# 51.net
KiCad netlist of a schematic drawn in Altium Designer
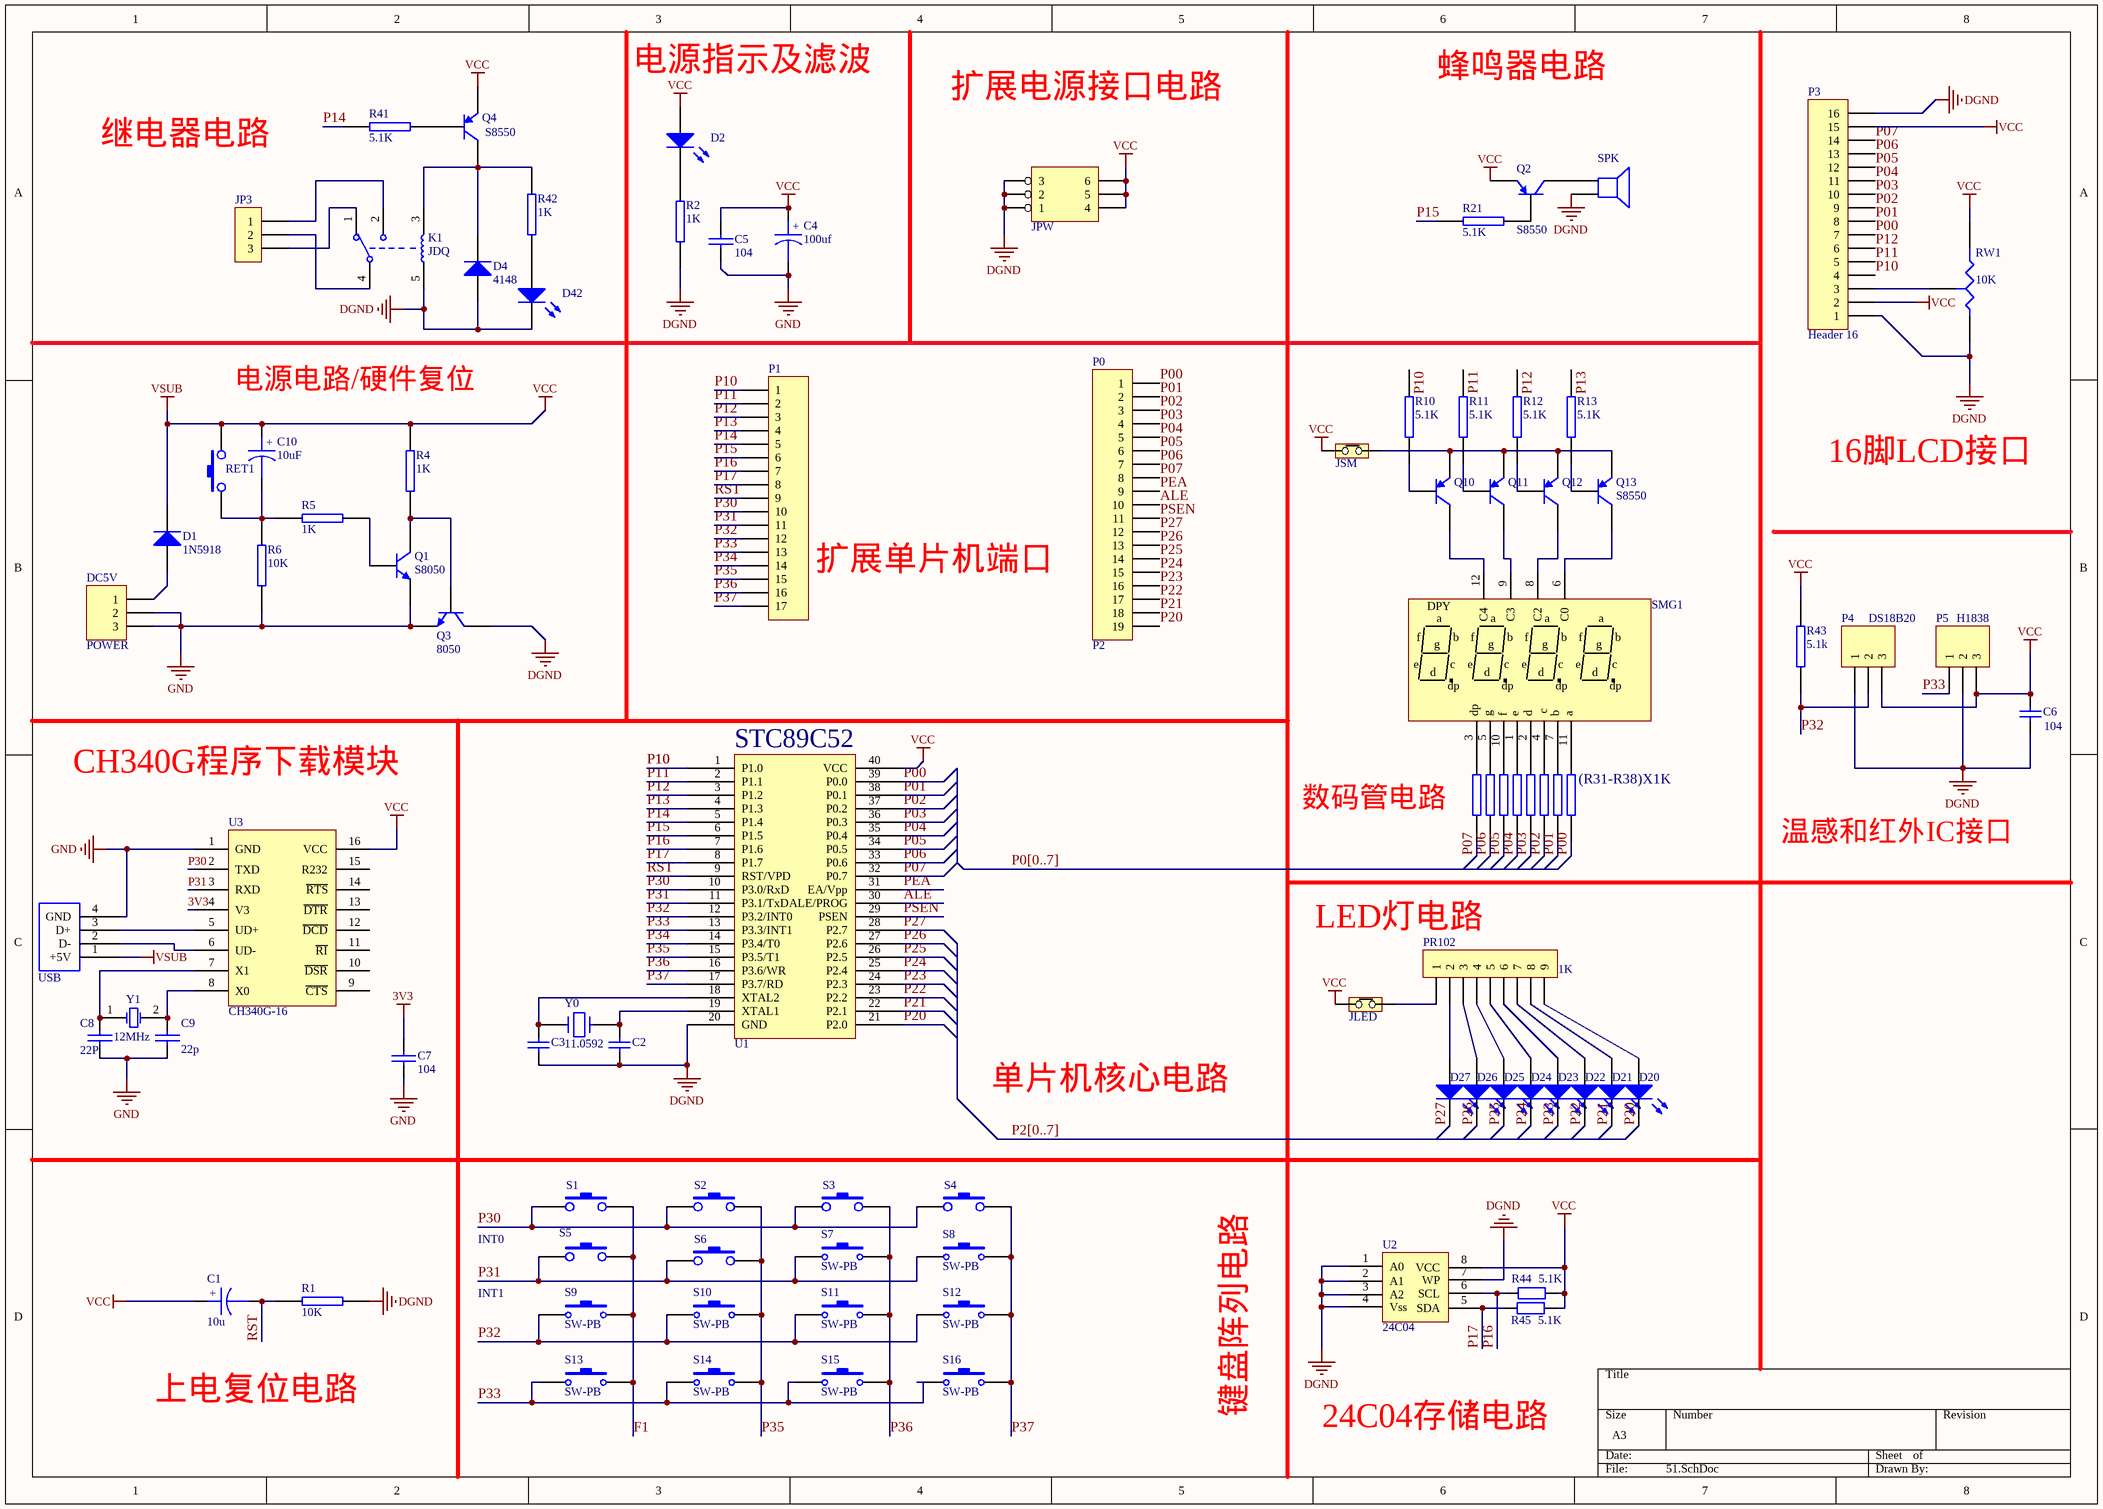
[diagram p0: 51.SchDoc]

(export (version "E")
  (design (tool "Eeschema 10.0.6"))
  (components
    (comp (ref "C1")
      (value "10u")
      (footprint "C2")
      (description "Capacitor")
      (libsource (lib "1") (part "CAPACITOR POL"))
    )
    (comp (ref "C2")
      (value "Cap")
      (footprint "RAD-0.1")
      (description "Capacitor")
      (fields
        (field (name "MANUFACTURER") "Generic Components")
        (field (name "PUBLISHER") "Altium Hobart Technology Centre")
      )
      (libsource (lib "Miscellaneous Devices") (part "Cap"))
    )
    (comp (ref "C3")
      (value "Cap")
      (footprint "RAD-0.1")
      (description "Capacitor")
      (fields
        (field (name "MANUFACTURER") "Generic Components")
        (field (name "PUBLISHER") "Altium Hobart Technology Centre")
      )
      (libsource (lib "Miscellaneous Devices") (part "Cap"))
    )
    (comp (ref "C4")
      (value "100uf")
      (footprint "c4")
      (description "Capacitor")
      (libsource (lib "1") (part "CAPACITOR POL"))
    )
    (comp (ref "C5")
      (value "104")
      (footprint "RAD-0.1")
      (description "Capacitor")
      (libsource (lib "1") (part "CAP"))
    )
    (comp (ref "C6")
      (value "104")
      (footprint "RAD-0.1")
      (description "Capacitor")
      (fields (field (name "Comment") "Cap") (field (name "PUBLISHER") "Altium Limited"))
      (libsource (lib "Miscellaneous Devices") (part "Cap"))
    )
    (comp (ref "C7")
      (value "104")
      (footprint "RAD-0.1")
      (description "Capacitor")
      (libsource (lib "Miscellaneous Devices") (part "CAP"))
    )
    (comp (ref "C8")
      (value "22P")
      (footprint "RAD-0.1")
      (description "Capacitor")
      (libsource (lib "Miscellaneous Devices") (part "CAP"))
    )
    (comp (ref "C9")
      (value "22p")
      (footprint "RAD-0.1")
      (description "Capacitor")
      (libsource (lib "Miscellaneous Devices") (part "CAP"))
    )
    (comp (ref "C10")
      (value "10uF")
      (footprint "c4")
      (description "Capacitor")
      (libsource (lib "1") (part "CAPACITOR POL"))
    )
    (comp (ref "D1")
      (value "1N5918")
      (footprint "4148")
      (description "3 Amp Medium Power Silicon Rectifier Diode")
      (fields (field (name "PUBLISHER") "Altium Limited"))
      (libsource (lib "Miscellaneous Devices") (part "Diode 1N5408"))
    )
    (comp (ref "D2")
      (value "LED0")
      (footprint "LED2")
      (description "Typical INFRARED GaAs LED")
      (fields (field (name "PUBLISHER") "Altium Limited"))
      (libsource (lib "Miscellaneous Devices") (part "LED0"))
    )
    (comp (ref "D4")
      (value "4148")
      (footprint "DO-41")
      (description "1 Amp General Purpose Rectifier")
      (fields (field (name "PUBLISHER") "Altium Limited"))
      (libsource (lib "Miscellaneous Devices") (part "Diode 1N4001"))
    )
    (comp (ref "D20")
      (value "LED0")
      (footprint "LED8")
      (description "Typical INFRARED GaAs LED")
      (fields (field (name "PUBLISHER") "Altium Limited"))
      (libsource (lib "Miscellaneous Devices") (part "LED0"))
    )
    (comp (ref "D21")
      (value "LED0")
      (footprint "LED8")
      (description "Typical INFRARED GaAs LED")
      (fields (field (name "PUBLISHER") "Altium Limited"))
      (libsource (lib "Miscellaneous Devices") (part "LED0"))
    )
    (comp (ref "D22")
      (value "LED0")
      (footprint "LED8")
      (description "Typical INFRARED GaAs LED")
      (fields (field (name "PUBLISHER") "Altium Limited"))
      (libsource (lib "Miscellaneous Devices") (part "LED0"))
    )
    (comp (ref "D23")
      (value "LED0")
      (footprint "LED8")
      (description "Typical INFRARED GaAs LED")
      (fields (field (name "PUBLISHER") "Altium Limited"))
      (libsource (lib "Miscellaneous Devices") (part "LED0"))
    )
    (comp (ref "D24")
      (value "LED0")
      (footprint "LED8")
      (description "Typical INFRARED GaAs LED")
      (fields (field (name "PUBLISHER") "Altium Limited"))
      (libsource (lib "Miscellaneous Devices") (part "LED0"))
    )
    (comp (ref "D25")
      (value "LED0")
      (footprint "LED8")
      (description "Typical INFRARED GaAs LED")
      (fields (field (name "PUBLISHER") "Altium Limited"))
      (libsource (lib "Miscellaneous Devices") (part "LED0"))
    )
    (comp (ref "D26")
      (value "LED0")
      (footprint "LED8")
      (description "Typical INFRARED GaAs LED")
      (fields (field (name "PUBLISHER") "Altium Limited"))
      (libsource (lib "Miscellaneous Devices") (part "LED0"))
    )
    (comp (ref "D27")
      (value "LED0")
      (footprint "LED8")
      (description "Typical INFRARED GaAs LED")
      (fields (field (name "PUBLISHER") "Altium Limited"))
      (libsource (lib "Miscellaneous Devices") (part "LED0"))
    )
    (comp (ref "D42")
      (value "LED0")
      (footprint "LED2")
      (description "Typical INFRARED GaAs LED")
      (fields (field (name "PUBLISHER") "Altium Limited"))
      (libsource (lib "Miscellaneous Devices") (part "LED0"))
    )
    (comp (ref "DC5V")
      (value "POWER")
      (footprint "DC5V-3")
      (description "Header, 3-Pin")
      (fields (field (name "PUBLISHER") "Altium Limited"))
      (libsource (lib "Miscellaneous Connectors") (part "Header 3"))
    )
    (comp (ref "JLED") (value "JJ") (footprint "j2") (libsource (lib "51单片机24_1") (part "JJ")))
    (comp (ref "JP3") (value "JP3") (footprint "JP3") (libsource (lib "51单片机24") (part "JP3")))
    (comp (ref "JPW") (value "JPW") (footprint "SIP") (libsource (lib "51单片机24_1") (part "JPW")))
    (comp (ref "JSM") (value "JJ") (footprint "j2") (libsource (lib "51单片机24_1") (part "JJ")))
    (comp (ref "K1") (value "JDQ") (footprint "JDQ") (libsource (lib "51单片机24_1") (part "JDQ")))
    (comp (ref "P0")
      (value "P2")
      (footprint "j19")
      (description "Header, 19-Pin")
      (fields (field (name "PUBLISHER") "Altium Limited"))
      (libsource (lib "单片机开发板") (part "Header 19"))
    )
    (comp (ref "P1")
      (value "Header 17")
      (footprint "j17")
      (description "Header, 17-Pin")
      (fields (field (name "PUBLISHER") "Altium Limited"))
      (libsource (lib "单片机开发板") (part "Header 17"))
    )
    (comp (ref "P3")
      (value "Header 16")
      (footprint "HDR1X16")
      (description "Header, 16-Pin")
      (fields (field (name "PUBLISHER") "Altium Limited"))
      (libsource (lib "Miscellaneous Connectors") (part "Header 16"))
    )
    (comp (ref "P4")
      (value "DS18B20")
      (footprint "HDR1X3")
      (description "Header, 3-Pin")
      (fields (field (name "PUBLISHER") "Altium Limited"))
      (libsource (lib "") (part "Header 3_1"))
    )
    (comp (ref "P5")
      (value "H1838")
      (footprint "HDR1X3")
      (description "Header, 3-Pin")
      (fields (field (name "PUBLISHER") "Altium Limited"))
      (libsource (lib "") (part "Header 3_1"))
    )
    (comp (ref "PR102")
      (value "1K")
      (footprint "SIP-9")
      (description "Connector")
      (libsource (lib "1") (part "CON9"))
    )
    (comp (ref "Q1")
      (value "S8050")
      (footprint "sanjiguan")
      (description "NPN General Purpose Amplifier")
      (fields (field (name "PUBLISHER") "Altium Limited"))
      (libsource (lib "Miscellaneous Devices") (part "2N3904"))
    )
    (comp (ref "Q2")
      (value "S8550")
      (footprint "sanjiguan")
      (description "PNP General Purpose Amplifier")
      (fields (field (name "PUBLISHER") "Altium Limited"))
      (libsource (lib "Miscellaneous Devices") (part "2N3906"))
    )
    (comp (ref "Q3")
      (value "8050")
      (footprint "sanjiguan")
      (description "NPN General Purpose Amplifier")
      (fields (field (name "PUBLISHER") "Altium Limited"))
      (libsource (lib "Miscellaneous Devices") (part "2N3904"))
    )
    (comp (ref "Q4")
      (value "S8550")
      (footprint "sanjiguan")
      (description "PNP General Purpose Amplifier")
      (fields (field (name "PUBLISHER") "Altium Limited"))
      (libsource (lib "Miscellaneous Devices") (part "2N3906"))
    )
    (comp (ref "Q10")
      (value "S8550")
      (footprint "sanjiguan")
      (description "PNP General Purpose Amplifier")
      (fields (field (name "PUBLISHER") "Altium Limited"))
      (libsource (lib "Miscellaneous Devices") (part "2N3906"))
    )
    (comp (ref "Q11")
      (value "S8550")
      (footprint "sanjiguan")
      (description "PNP General Purpose Amplifier")
      (fields (field (name "PUBLISHER") "Altium Limited"))
      (libsource (lib "Miscellaneous Devices") (part "2N3906"))
    )
    (comp (ref "Q12")
      (value "S8550")
      (footprint "sanjiguan")
      (description "PNP General Purpose Amplifier")
      (fields (field (name "PUBLISHER") "Altium Limited"))
      (libsource (lib "Miscellaneous Devices") (part "2N3906"))
    )
    (comp (ref "Q13")
      (value "S8550")
      (footprint "sanjiguan")
      (description "PNP General Purpose Amplifier")
      (fields (field (name "PUBLISHER") "Altium Limited"))
      (libsource (lib "Miscellaneous Devices") (part "2N3906"))
    )
    (comp (ref "R1")
      (value "10K")
      (footprint "axial0.4")
      (libsource (lib "Miscellaneous Devices") (part "RES2"))
    )
    (comp (ref "R2") (value "1K") (footprint "axial0.4") (libsource (lib "1") (part "RES2")))
    (comp (ref "R4")
      (value "1K")
      (footprint "axial0.4")
      (libsource (lib "Miscellaneous Devices") (part "RES2"))
    )
    (comp (ref "R5")
      (value "1K")
      (footprint "axial0.4")
      (libsource (lib "Miscellaneous Devices") (part "RES2"))
    )
    (comp (ref "R6")
      (value "10K")
      (footprint "axial0.4")
      (libsource (lib "Miscellaneous Devices") (part "RES2"))
    )
    (comp (ref "R10")
      (value "5.1K")
      (footprint "axial0.4")
      (libsource (lib "Miscellaneous Devices") (part "RES2"))
    )
    (comp (ref "R11")
      (value "5.1K")
      (footprint "axial0.4")
      (libsource (lib "Miscellaneous Devices") (part "RES2"))
    )
    (comp (ref "R12")
      (value "5.1K")
      (footprint "axial0.4")
      (libsource (lib "Miscellaneous Devices") (part "RES2"))
    )
    (comp (ref "R13")
      (value "5.1K")
      (footprint "axial0.4")
      (libsource (lib "Miscellaneous Devices") (part "RES2"))
    )
    (comp (ref "R21")
      (value "5.1K")
      (footprint "axial0.4")
      (libsource (lib "Miscellaneous Devices") (part "RES2"))
    )
    (comp (ref "R31")
      (value "1K")
      (footprint "axial0.4")
      (libsource (lib "Miscellaneous Devices") (part "RES2"))
    )
    (comp (ref "R32")
      (value "1K")
      (footprint "axial0.4")
      (libsource (lib "Miscellaneous Devices") (part "RES2"))
    )
    (comp (ref "R33")
      (value "1K")
      (footprint "axial0.4")
      (libsource (lib "Miscellaneous Devices") (part "RES2"))
    )
    (comp (ref "R34")
      (value "1K")
      (footprint "axial0.4")
      (libsource (lib "Miscellaneous Devices") (part "RES2"))
    )
    (comp (ref "R35")
      (value "1K")
      (footprint "axial0.4")
      (libsource (lib "Miscellaneous Devices") (part "RES2"))
    )
    (comp (ref "R36")
      (value "1K")
      (footprint "axial0.4")
      (libsource (lib "Miscellaneous Devices") (part "RES2"))
    )
    (comp (ref "R37")
      (value "1K")
      (footprint "axial0.4")
      (libsource (lib "Miscellaneous Devices") (part "RES2"))
    )
    (comp (ref "R38")
      (value "1K")
      (footprint "axial0.4")
      (libsource (lib "Miscellaneous Devices") (part "RES2"))
    )
    (comp (ref "R41")
      (value "5.1K")
      (footprint "axial0.4")
      (libsource (lib "Miscellaneous Devices") (part "RES2"))
    )
    (comp (ref "R42")
      (value "1K")
      (footprint "axial0.4")
      (libsource (lib "Miscellaneous Devices") (part "RES2"))
    )
    (comp (ref "R43")
      (value "5.1k")
      (footprint "axial0.4")
      (libsource (lib "Miscellaneous Devices") (part "RES2"))
    )
    (comp (ref "R44")
      (value "5.1K")
      (footprint "AXIAL-0.4")
      (description "Resistor")
      (fields (field (name "PUBLISHER") "Altium Limited"))
      (libsource (lib "Miscellaneous Devices") (part "Res2"))
    )
    (comp (ref "R45")
      (value "5.1K")
      (footprint "AXIAL-0.4")
      (description "Resistor")
      (fields (field (name "PUBLISHER") "Altium Limited"))
      (libsource (lib "Miscellaneous Devices") (part "Res2"))
    )
    (comp (ref "RET1") (value "RET") (footprint "sw") (libsource (lib "") (part "SW-PB_1")))
    (comp (ref "RW1")
      (value "10K")
      (footprint "RW")
      (description "Tapped Resistor")
      (fields (field (name "Comment") "Res Tap") (field (name "PUBLISHER") "Altium Limited"))
      (libsource (lib "Miscellaneous Devices") (part "Res Tap"))
    )
    (comp (ref "S1") (value "RET") (footprint "sw") (libsource (lib "") (part "SW-PB_1")))
    (comp (ref "S2") (value "RET") (footprint "sw") (libsource (lib "") (part "SW-PB_1")))
    (comp (ref "S3") (value "RET") (footprint "sw") (libsource (lib "") (part "SW-PB_1")))
    (comp (ref "S4") (value "RET") (footprint "sw") (libsource (lib "") (part "SW-PB_1")))
    (comp (ref "S5") (value "RET") (footprint "sw") (libsource (lib "") (part "SW-PB_1")))
    (comp (ref "S6") (value "RET") (footprint "sw") (libsource (lib "") (part "SW-PB_1")))
    (comp (ref "S7")
      (value "SW-PB")
      (footprint "SW")
      (description "Switch")
      (fields (field (name "PUBLISHER") "Altium Limited"))
      (libsource (lib "Miscellaneous Devices") (part "SW-PB"))
    )
    (comp (ref "S8")
      (value "SW-PB")
      (footprint "SW")
      (description "Switch")
      (fields (field (name "PUBLISHER") "Altium Limited"))
      (libsource (lib "Miscellaneous Devices") (part "SW-PB"))
    )
    (comp (ref "S9")
      (value "SW-PB")
      (footprint "SW")
      (description "Switch")
      (fields (field (name "PUBLISHER") "Altium Limited"))
      (libsource (lib "Miscellaneous Devices") (part "SW-PB"))
    )
    (comp (ref "S10")
      (value "SW-PB")
      (footprint "SW")
      (description "Switch")
      (fields (field (name "PUBLISHER") "Altium Limited"))
      (libsource (lib "Miscellaneous Devices") (part "SW-PB"))
    )
    (comp (ref "S11")
      (value "SW-PB")
      (footprint "SW")
      (description "Switch")
      (fields (field (name "PUBLISHER") "Altium Limited"))
      (libsource (lib "Miscellaneous Devices") (part "SW-PB"))
    )
    (comp (ref "S12")
      (value "SW-PB")
      (footprint "SW")
      (description "Switch")
      (fields (field (name "PUBLISHER") "Altium Limited"))
      (libsource (lib "Miscellaneous Devices") (part "SW-PB"))
    )
    (comp (ref "S13")
      (value "SW-PB")
      (footprint "SW")
      (description "Switch")
      (fields (field (name "PUBLISHER") "Altium Limited"))
      (libsource (lib "Miscellaneous Devices") (part "SW-PB"))
    )
    (comp (ref "S14")
      (value "SW-PB")
      (footprint "SW")
      (description "Switch")
      (fields (field (name "PUBLISHER") "Altium Limited"))
      (libsource (lib "Miscellaneous Devices") (part "SW-PB"))
    )
    (comp (ref "S15")
      (value "SW-PB")
      (footprint "SW")
      (description "Switch")
      (fields (field (name "PUBLISHER") "Altium Limited"))
      (libsource (lib "Miscellaneous Devices") (part "SW-PB"))
    )
    (comp (ref "S16")
      (value "SW-PB")
      (footprint "SW")
      (description "Switch")
      (fields (field (name "PUBLISHER") "Altium Limited"))
      (libsource (lib "Miscellaneous Devices") (part "SW-PB"))
    )
    (comp (ref "SMG1") (value "SMG") (footprint "smg") (libsource (lib "51单片机24") (part "SMG")))
    (comp (ref "SPK")
      (value "Speaker")
      (footprint "HDR1X4")
      (libsource (lib "Miscellaneous Devices") (part "SPEAKER"))
    )
    (comp (ref "STC89C52") (value "U1") (footprint "S52") (libsource (lib "51单片机24_1") (part "89C51")))
    (comp (ref "U2") (value "24C04") (footprint "DIP8") (libsource (lib "51单片机24_1") (part "24C04")))
    (comp (ref "U3")
      (value "CH340G-16")
      (footprint "SOP-16 - duplicate")
      (libsource (lib "51单片机24_1") (part "CH340G-16"))
    )
    (comp (ref "USB")
      (value "CON4")
      (footprint "USB")
      (description "Connector")
      (libsource (lib "1") (part "CON4"))
    )
    (comp (ref "Y0")
      (value "11.0592")
      (footprint "XTAL1")
      (description "Crystal")
      (libsource (lib "1") (part "CRYSTAL"))
    )
    (comp (ref "Y1")
      (value "12MHz")
      (footprint "XTAL1")
      (description "Crystal Oscillator")
      (fields (field (name "PUBLISHER") "Altium Limited"))
      (libsource (lib "Miscellaneous Devices") (part "XTAL"))
    )
  )
  (nets
    (net (code "1") (name "/ALE") (class "Default")
      (node (ref "P0") (pin "10") (pinfunction "10_10") (pintype "passive"))
      (node (ref "STC89C52") (pin "30") (pinfunction "ALE/PROG_30") (pintype "passive"))
    )
    (net (code "2") (name "/F1") (class "Default")
      (node (ref "S1") (pin "2") (pinfunction "2_2") (pintype "passive"))
      (node (ref "S13") (pin "2") (pinfunction "2_2") (pintype "passive"))
      (node (ref "S5") (pin "2") (pinfunction "2_2") (pintype "passive"))
      (node (ref "S9") (pin "2") (pinfunction "2_2") (pintype "passive"))
    )
    (net (code "3") (name "/P00") (class "Default")
      (node (ref "P0") (pin "1") (pinfunction "1_1") (pintype "passive"))
      (node (ref "P3") (pin "7") (pinfunction "7_7") (pintype "passive"))
      (node (ref "R31") (pin "1") (pinfunction "1_1") (pintype "passive"))
      (node (ref "STC89C52") (pin "39") (pinfunction "P0.0_39") (pintype "passive"))
    )
    (net (code "5") (name "/P01") (class "Default")
      (node (ref "P0") (pin "2") (pinfunction "2_2") (pintype "passive"))
      (node (ref "P3") (pin "8") (pinfunction "8_8") (pintype "passive"))
      (node (ref "R32") (pin "1") (pinfunction "1_1") (pintype "passive"))
      (node (ref "STC89C52") (pin "38") (pinfunction "P0.1_38") (pintype "passive"))
    )
    (net (code "6") (name "/P02") (class "Default")
      (node (ref "P0") (pin "3") (pinfunction "3_3") (pintype "passive"))
      (node (ref "P3") (pin "9") (pinfunction "9_9") (pintype "passive"))
      (node (ref "R33") (pin "1") (pinfunction "1_1") (pintype "passive"))
      (node (ref "STC89C52") (pin "37") (pinfunction "P0.2_37") (pintype "passive"))
    )
    (net (code "8") (name "/P03") (class "Default")
      (node (ref "P0") (pin "4") (pinfunction "4_4") (pintype "passive"))
      (node (ref "P3") (pin "10") (pinfunction "10_10") (pintype "passive"))
      (node (ref "R34") (pin "1") (pinfunction "1_1") (pintype "passive"))
      (node (ref "STC89C52") (pin "36") (pinfunction "P0.3_36") (pintype "passive"))
    )
    (net (code "9") (name "/P04") (class "Default")
      (node (ref "P0") (pin "5") (pinfunction "5_5") (pintype "passive"))
      (node (ref "P3") (pin "11") (pinfunction "11_11") (pintype "passive"))
      (node (ref "R35") (pin "1") (pinfunction "1_1") (pintype "passive"))
      (node (ref "STC89C52") (pin "35") (pinfunction "P0.4_35") (pintype "passive"))
    )
    (net (code "10") (name "/P05") (class "Default")
      (node (ref "P0") (pin "6") (pinfunction "6_6") (pintype "passive"))
      (node (ref "P3") (pin "12") (pinfunction "12_12") (pintype "passive"))
      (node (ref "R36") (pin "1") (pinfunction "1_1") (pintype "passive"))
      (node (ref "STC89C52") (pin "34") (pinfunction "P0.5_34") (pintype "passive"))
    )
    (net (code "11") (name "/P06") (class "Default")
      (node (ref "P0") (pin "7") (pinfunction "7_7") (pintype "passive"))
      (node (ref "P3") (pin "13") (pinfunction "13_13") (pintype "passive"))
      (node (ref "R37") (pin "1") (pinfunction "1_1") (pintype "passive"))
      (node (ref "STC89C52") (pin "33") (pinfunction "P0.6_33") (pintype "passive"))
    )
    (net (code "12") (name "/P07") (class "Default")
      (node (ref "P0") (pin "8") (pinfunction "8_8") (pintype "passive"))
      (node (ref "P3") (pin "14") (pinfunction "14_14") (pintype "passive"))
      (node (ref "R38") (pin "1") (pinfunction "1_1") (pintype "passive"))
      (node (ref "STC89C52") (pin "32") (pinfunction "P0.7_32") (pintype "passive"))
    )
    (net (code "13") (name "/P10") (class "Default")
      (node (ref "P1") (pin "1") (pinfunction "1_1") (pintype "passive"))
      (node (ref "P3") (pin "4") (pinfunction "4_4") (pintype "passive"))
      (node (ref "R10") (pin "2") (pinfunction "2_2") (pintype "passive"))
      (node (ref "STC89C52") (pin "1") (pinfunction "P1.0_1") (pintype "passive"))
    )
    (net (code "14") (name "/P11") (class "Default")
      (node (ref "P1") (pin "2") (pinfunction "2_2") (pintype "passive"))
      (node (ref "P3") (pin "5") (pinfunction "5_5") (pintype "passive"))
      (node (ref "R11") (pin "2") (pinfunction "2_2") (pintype "passive"))
      (node (ref "STC89C52") (pin "2") (pinfunction "P1.1_2") (pintype "passive"))
    )
    (net (code "15") (name "/P12") (class "Default")
      (node (ref "P1") (pin "3") (pinfunction "3_3") (pintype "passive"))
      (node (ref "P3") (pin "6") (pinfunction "6_6") (pintype "passive"))
      (node (ref "R12") (pin "2") (pinfunction "2_2") (pintype "passive"))
      (node (ref "STC89C52") (pin "3") (pinfunction "P1.2_3") (pintype "passive"))
    )
    (net (code "16") (name "/P13") (class "Default")
      (node (ref "P1") (pin "4") (pinfunction "4_4") (pintype "passive"))
      (node (ref "R13") (pin "2") (pinfunction "2_2") (pintype "passive"))
      (node (ref "STC89C52") (pin "4") (pinfunction "P1.3_4") (pintype "passive"))
    )
    (net (code "17") (name "/P14") (class "Default")
      (node (ref "P1") (pin "5") (pinfunction "5_5") (pintype "passive"))
      (node (ref "R41") (pin "1") (pinfunction "1_1") (pintype "passive"))
      (node (ref "STC89C52") (pin "5") (pinfunction "P1.4_5") (pintype "passive"))
    )
    (net (code "18") (name "/P15") (class "Default")
      (node (ref "P1") (pin "6") (pinfunction "6_6") (pintype "passive"))
      (node (ref "R21") (pin "1") (pinfunction "1_1") (pintype "passive"))
      (node (ref "STC89C52") (pin "6") (pinfunction "P1.5_6") (pintype "passive"))
    )
    (net (code "19") (name "/P16") (class "Default")
      (node (ref "P1") (pin "7") (pinfunction "7_7") (pintype "passive"))
      (node (ref "R44") (pin "1") (pinfunction "1_1") (pintype "passive"))
      (node (ref "STC89C52") (pin "7") (pinfunction "P1.6_7") (pintype "passive"))
      (node (ref "U2") (pin "6") (pinfunction "SCL_6") (pintype "passive"))
    )
    (net (code "20") (name "/P17") (class "Default")
      (node (ref "P1") (pin "8") (pinfunction "8_8") (pintype "passive"))
      (node (ref "R45") (pin "1") (pinfunction "1_1") (pintype "passive"))
      (node (ref "STC89C52") (pin "8") (pinfunction "P1.7_8") (pintype "passive"))
      (node (ref "U2") (pin "5") (pinfunction "SDA_5") (pintype "passive"))
    )
    (net (code "21") (name "/P20") (class "Default")
      (node (ref "D20") (pin "2") (pinfunction "K_2") (pintype "passive"))
      (node (ref "P0") (pin "19") (pinfunction "19_19") (pintype "passive"))
      (node (ref "STC89C52") (pin "21") (pinfunction "P2.0_21") (pintype "passive"))
    )
    (net (code "22") (name "/P21") (class "Default")
      (node (ref "D21") (pin "2") (pinfunction "K_2") (pintype "passive"))
      (node (ref "P0") (pin "18") (pinfunction "18_18") (pintype "passive"))
      (node (ref "STC89C52") (pin "22") (pinfunction "P2.1_22") (pintype "passive"))
    )
    (net (code "23") (name "/P22") (class "Default")
      (node (ref "D22") (pin "2") (pinfunction "K_2") (pintype "passive"))
      (node (ref "P0") (pin "17") (pinfunction "17_17") (pintype "passive"))
      (node (ref "STC89C52") (pin "23") (pinfunction "P2.2_23") (pintype "passive"))
    )
    (net (code "24") (name "/P23") (class "Default")
      (node (ref "D23") (pin "2") (pinfunction "K_2") (pintype "passive"))
      (node (ref "P0") (pin "16") (pinfunction "16_16") (pintype "passive"))
      (node (ref "STC89C52") (pin "24") (pinfunction "P2.3_24") (pintype "passive"))
    )
    (net (code "25") (name "/P24") (class "Default")
      (node (ref "D24") (pin "2") (pinfunction "K_2") (pintype "passive"))
      (node (ref "P0") (pin "15") (pinfunction "15_15") (pintype "passive"))
      (node (ref "STC89C52") (pin "25") (pinfunction "P2.4_25") (pintype "passive"))
    )
    (net (code "26") (name "/P25") (class "Default")
      (node (ref "D25") (pin "2") (pinfunction "K_2") (pintype "passive"))
      (node (ref "P0") (pin "14") (pinfunction "14_14") (pintype "passive"))
      (node (ref "STC89C52") (pin "26") (pinfunction "P2.5_26") (pintype "passive"))
    )
    (net (code "27") (name "/P26") (class "Default")
      (node (ref "D26") (pin "2") (pinfunction "K_2") (pintype "passive"))
      (node (ref "P0") (pin "13") (pinfunction "13_13") (pintype "passive"))
      (node (ref "STC89C52") (pin "27") (pinfunction "P2.6_27") (pintype "passive"))
    )
    (net (code "28") (name "/P27") (class "Default")
      (node (ref "D27") (pin "2") (pinfunction "K_2") (pintype "passive"))
      (node (ref "P0") (pin "12") (pinfunction "12_12") (pintype "passive"))
      (node (ref "STC89C52") (pin "28") (pinfunction "P2.7_28") (pintype "passive"))
    )
    (net (code "29") (name "/P30") (class "Default")
      (node (ref "P1") (pin "10") (pinfunction "10_10") (pintype "passive"))
      (node (ref "S1") (pin "1") (pinfunction "1_1") (pintype "passive"))
      (node (ref "S2") (pin "1") (pinfunction "1_1") (pintype "passive"))
      (node (ref "S3") (pin "1") (pinfunction "1_1") (pintype "passive"))
      (node (ref "S4") (pin "1") (pinfunction "1_1") (pintype "passive"))
      (node (ref "STC89C52") (pin "10") (pinfunction "P3.0/RxD_10") (pintype "passive"))
      (node (ref "U3") (pin "2") (pinfunction "TXD_2") (pintype "passive"))
    )
    (net (code "30") (name "/P31") (class "Default")
      (node (ref "P1") (pin "11") (pinfunction "11_11") (pintype "passive"))
      (node (ref "S5") (pin "1") (pinfunction "1_1") (pintype "passive"))
      (node (ref "S6") (pin "1") (pinfunction "1_1") (pintype "passive"))
      (node (ref "S7") (pin "1") (pinfunction "1_1") (pintype "passive"))
      (node (ref "S8") (pin "1") (pinfunction "1_1") (pintype "passive"))
      (node (ref "STC89C52") (pin "11") (pinfunction "P3.1/TxD_11") (pintype "passive"))
      (node (ref "U3") (pin "3") (pinfunction "RXD_3") (pintype "passive"))
    )
    (net (code "31") (name "/P32") (class "Default")
      (node (ref "P1") (pin "12") (pinfunction "12_12") (pintype "passive"))
      (node (ref "P4") (pin "2") (pinfunction "2_2") (pintype "passive"))
      (node (ref "R43") (pin "1") (pinfunction "1_1") (pintype "passive"))
      (node (ref "S10") (pin "1") (pinfunction "1_1") (pintype "passive"))
      (node (ref "S11") (pin "1") (pinfunction "1_1") (pintype "passive"))
      (node (ref "S12") (pin "1") (pinfunction "1_1") (pintype "passive"))
      (node (ref "S9") (pin "1") (pinfunction "1_1") (pintype "passive"))
      (node (ref "STC89C52") (pin "12") (pinfunction "P3.2/INT0_12") (pintype "passive"))
    )
    (net (code "32") (name "/P33") (class "Default")
      (node (ref "P1") (pin "13") (pinfunction "13_13") (pintype "passive"))
      (node (ref "P5") (pin "1") (pinfunction "1_1") (pintype "passive"))
      (node (ref "S13") (pin "1") (pinfunction "1_1") (pintype "passive"))
      (node (ref "S14") (pin "1") (pinfunction "1_1") (pintype "passive"))
      (node (ref "S15") (pin "1") (pinfunction "1_1") (pintype "passive"))
      (node (ref "S16") (pin "1") (pinfunction "1_1") (pintype "passive"))
      (node (ref "STC89C52") (pin "13") (pinfunction "P3.3/INT1_13") (pintype "passive"))
    )
    (net (code "33") (name "/P34") (class "Default")
      (node (ref "P1") (pin "14") (pinfunction "14_14") (pintype "passive"))
      (node (ref "STC89C52") (pin "14") (pinfunction "P3.4/T0_14") (pintype "passive"))
    )
    (net (code "34") (name "/P35") (class "Default")
      (node (ref "P1") (pin "15") (pinfunction "15_15") (pintype "passive"))
      (node (ref "S10") (pin "2") (pinfunction "2_2") (pintype "passive"))
      (node (ref "S14") (pin "2") (pinfunction "2_2") (pintype "passive"))
      (node (ref "S2") (pin "2") (pinfunction "2_2") (pintype "passive"))
      (node (ref "S6") (pin "2") (pinfunction "2_2") (pintype "passive"))
      (node (ref "STC89C52") (pin "15") (pinfunction "P3.5/T1_15") (pintype "passive"))
    )
    (net (code "35") (name "/P36") (class "Default")
      (node (ref "P1") (pin "16") (pinfunction "16_16") (pintype "passive"))
      (node (ref "S11") (pin "2") (pinfunction "2_2") (pintype "passive"))
      (node (ref "S15") (pin "2") (pinfunction "2_2") (pintype "passive"))
      (node (ref "S3") (pin "2") (pinfunction "2_2") (pintype "passive"))
      (node (ref "S7") (pin "2") (pinfunction "2_2") (pintype "passive"))
      (node (ref "STC89C52") (pin "16") (pinfunction "P3.6/WR_16") (pintype "passive"))
    )
    (net (code "36") (name "/P37") (class "Default")
      (node (ref "P1") (pin "17") (pinfunction "17_17") (pintype "passive"))
      (node (ref "S12") (pin "2") (pinfunction "2_2") (pintype "passive"))
      (node (ref "S16") (pin "2") (pinfunction "2_2") (pintype "passive"))
      (node (ref "S4") (pin "2") (pinfunction "2_2") (pintype "passive"))
      (node (ref "S8") (pin "2") (pinfunction "2_2") (pintype "passive"))
      (node (ref "STC89C52") (pin "17") (pinfunction "P3.7/RD_17") (pintype "passive"))
    )
    (net (code "37") (name "/PEA") (class "Default")
      (node (ref "P0") (pin "9") (pinfunction "9_9") (pintype "passive"))
      (node (ref "STC89C52") (pin "31") (pinfunction "EA/Vpp_31") (pintype "passive"))
    )
    (net (code "38") (name "/PSEN") (class "Default")
      (node (ref "P0") (pin "11") (pinfunction "11_11") (pintype "passive"))
      (node (ref "STC89C52") (pin "29") (pinfunction "PSEN_29") (pintype "passive"))
    )
    (net (code "39") (name "/RST") (class "Default")
      (node (ref "C1") (pin "2") (pinfunction "2_2") (pintype "passive"))
      (node (ref "P1") (pin "9") (pinfunction "9_9") (pintype "passive"))
      (node (ref "R1") (pin "2") (pinfunction "2_2") (pintype "passive"))
      (node (ref "STC89C52") (pin "9") (pinfunction "RST/VPD_9") (pintype "passive"))
    )
    (net (code "40") (name "3V3") (class "Default")
      (node (ref "C7") (pin "1") (pinfunction "1_1") (pintype "passive"))
      (node (ref "U3") (pin "4") (pinfunction "V3_4") (pintype "passive"))
    )
    (net (code "41") (name "DGND") (class "Default")
      (node (ref "C2") (pin "1") (pinfunction "1_1") (pintype "passive"))
      (node (ref "C3") (pin "1") (pinfunction "1_1") (pintype "passive"))
      (node (ref "C6") (pin "1") (pinfunction "1_1") (pintype "passive"))
      (node (ref "D4") (pin "1") (pinfunction "A_1") (pintype "passive"))
      (node (ref "D42") (pin "2") (pinfunction "K_2") (pintype "passive"))
      (node (ref "JPW") (pin "1") (pinfunction "1_1") (pintype "passive"))
      (node (ref "JPW") (pin "2") (pinfunction "2_2") (pintype "passive"))
      (node (ref "JPW") (pin "3") (pinfunction "3_3") (pintype "passive"))
      (node (ref "K1") (pin "5") (pinfunction "5_5") (pintype "passive"))
      (node (ref "P3") (pin "1") (pinfunction "1_1") (pintype "passive"))
      (node (ref "P3") (pin "16") (pinfunction "16_16") (pintype "passive"))
      (node (ref "P4") (pin "1") (pinfunction "1_1") (pintype "passive"))
      (node (ref "P5") (pin "2") (pinfunction "2_2") (pintype "passive"))
      (node (ref "Q3") (pin "3") (pinfunction "C_3") (pintype "passive"))
      (node (ref "R1") (pin "1") (pinfunction "1_1") (pintype "passive"))
      (node (ref "R2") (pin "1") (pinfunction "1_1") (pintype "passive"))
      (node (ref "RW1") (pin "1") (pinfunction "A_1") (pintype "passive"))
      (node (ref "SPK") (pin "2") (pinfunction "K_2") (pintype "passive"))
      (node (ref "STC89C52") (pin "20") (pinfunction "GND_20") (pintype "passive"))
      (node (ref "U2") (pin "1") (pinfunction "A0_1") (pintype "passive"))
      (node (ref "U2") (pin "2") (pinfunction "A1_2") (pintype "passive"))
      (node (ref "U2") (pin "3") (pinfunction "A2_3") (pintype "passive"))
      (node (ref "U2") (pin "4") (pinfunction "Vss_4") (pintype "passive"))
      (node (ref "U2") (pin "7") (pinfunction "WP_7") (pintype "passive"))
    )
    (net (code "42") (name "GND") (class "Default")
      (node (ref "C4") (pin "2") (pinfunction "2_2") (pintype "passive"))
      (node (ref "C5") (pin "2") (pinfunction "2_2") (pintype "passive"))
      (node (ref "C7") (pin "2") (pinfunction "2_2") (pintype "passive"))
      (node (ref "C8") (pin "2") (pinfunction "2_2") (pintype "passive"))
      (node (ref "C9") (pin "2") (pinfunction "2_2") (pintype "passive"))
      (node (ref "DC5V") (pin "2") (pinfunction "2_2") (pintype "passive"))
      (node (ref "DC5V") (pin "3") (pinfunction "3_3") (pintype "passive"))
      (node (ref "Q1") (pin "1") (pinfunction "E_1") (pintype "passive"))
      (node (ref "Q3") (pin "1") (pinfunction "E_1") (pintype "passive"))
      (node (ref "R6") (pin "2") (pinfunction "2_2") (pintype "passive"))
      (node (ref "U3") (pin "1") (pinfunction "GND_1") (pintype "passive"))
      (node (ref "USB") (pin "4") (pinfunction "GND_4") (pintype "passive"))
    )
    (net (code "43") (name "Net-(C10-Pad2)") (class "Default")
      (node (ref "C10") (pin "2") (pinfunction "2_2") (pintype "passive"))
      (node (ref "R5") (pin "1") (pinfunction "1_1") (pintype "passive"))
      (node (ref "R6") (pin "1") (pinfunction "1_1") (pintype "passive"))
      (node (ref "RET1") (pin "1") (pinfunction "1_1") (pintype "passive"))
    )
    (net (code "44") (name "Net-(D1-A)") (class "Default")
      (node (ref "D1") (pin "1") (pinfunction "A_1") (pintype "passive"))
      (node (ref "DC5V") (pin "1") (pinfunction "1_1") (pintype "passive"))
    )
    (net (code "45") (name "Net-(D2-K)") (class "Default")
      (node (ref "D2") (pin "2") (pinfunction "K_2") (pintype "passive"))
      (node (ref "R2") (pin "2") (pinfunction "2_2") (pintype "passive"))
    )
    (net (code "46") (name "Net-(D4-K)") (class "Default")
      (node (ref "D4") (pin "2") (pinfunction "K_2") (pintype "passive"))
      (node (ref "K1") (pin "3") (pinfunction "3_3") (pintype "passive"))
      (node (ref "Q4") (pin "3") (pinfunction "C_3") (pintype "passive"))
      (node (ref "R42") (pin "2") (pinfunction "2_2") (pintype "passive"))
    )
    (net (code "47") (name "Net-(D20-A)") (class "Default")
      (node (ref "D20") (pin "1") (pinfunction "A_1") (pintype "passive"))
      (node (ref "PR102") (pin "9") (pinfunction "9_9") (pintype "passive"))
    )
    (net (code "48") (name "Net-(D21-A)") (class "Default")
      (node (ref "D21") (pin "1") (pinfunction "A_1") (pintype "passive"))
      (node (ref "PR102") (pin "8") (pinfunction "8_8") (pintype "passive"))
    )
    (net (code "49") (name "Net-(D22-A)") (class "Default")
      (node (ref "D22") (pin "1") (pinfunction "A_1") (pintype "passive"))
      (node (ref "PR102") (pin "7") (pinfunction "7_7") (pintype "passive"))
    )
    (net (code "50") (name "Net-(D23-A)") (class "Default")
      (node (ref "D23") (pin "1") (pinfunction "A_1") (pintype "passive"))
      (node (ref "PR102") (pin "6") (pinfunction "6_6") (pintype "passive"))
    )
    (net (code "51") (name "Net-(D24-A)") (class "Default")
      (node (ref "D24") (pin "1") (pinfunction "A_1") (pintype "passive"))
      (node (ref "PR102") (pin "5") (pinfunction "5_5") (pintype "passive"))
    )
    (net (code "52") (name "Net-(D25-A)") (class "Default")
      (node (ref "D25") (pin "1") (pinfunction "A_1") (pintype "passive"))
      (node (ref "PR102") (pin "4") (pinfunction "4_4") (pintype "passive"))
    )
    (net (code "53") (name "Net-(D26-A)") (class "Default")
      (node (ref "D26") (pin "1") (pinfunction "A_1") (pintype "passive"))
      (node (ref "PR102") (pin "3") (pinfunction "3_3") (pintype "passive"))
    )
    (net (code "54") (name "Net-(D27-A)") (class "Default")
      (node (ref "D27") (pin "1") (pinfunction "A_1") (pintype "passive"))
      (node (ref "PR102") (pin "2") (pinfunction "2_2") (pintype "passive"))
    )
    (net (code "55") (name "Net-(D42-A)") (class "Default")
      (node (ref "D42") (pin "1") (pinfunction "A_1") (pintype "passive"))
      (node (ref "R42") (pin "1") (pinfunction "1_1") (pintype "passive"))
    )
    (net (code "56") (name "Net-(JLED-Pad2)") (class "Default")
      (node (ref "JLED") (pin "2") (pinfunction "2_2") (pintype "passive"))
      (node (ref "PR102") (pin "1") (pinfunction "1_1") (pintype "passive"))
    )
    (net (code "57") (name "Net-(JP3-Pad1)") (class "Default")
      (node (ref "JP3") (pin "1") (pinfunction "1_1") (pintype "passive"))
      (node (ref "K1") (pin "2") (pinfunction "2_2") (pintype "passive"))
    )
    (net (code "58") (name "Net-(JP3-Pad2)") (class "Default")
      (node (ref "JP3") (pin "2") (pinfunction "2_2") (pintype "passive"))
      (node (ref "K1") (pin "4") (pinfunction "4_4") (pintype "passive"))
    )
    (net (code "59") (name "Net-(JP3-Pad3)") (class "Default")
      (node (ref "JP3") (pin "3") (pinfunction "3_3") (pintype "passive"))
      (node (ref "K1") (pin "1") (pinfunction "1_1") (pintype "passive"))
    )
    (net (code "60") (name "Net-(Q1-B)") (class "Default")
      (node (ref "Q1") (pin "2") (pinfunction "B_2") (pintype "passive"))
      (node (ref "R5") (pin "2") (pinfunction "2_2") (pintype "passive"))
    )
    (net (code "61") (name "Net-(Q1-C)") (class "Default")
      (node (ref "Q1") (pin "3") (pinfunction "C_3") (pintype "passive"))
      (node (ref "Q3") (pin "2") (pinfunction "B_2") (pintype "passive"))
      (node (ref "R4") (pin "1") (pinfunction "1_1") (pintype "passive"))
    )
    (net (code "62") (name "Net-(Q2-B)") (class "Default")
      (node (ref "Q2") (pin "2") (pinfunction "B_2") (pintype "passive"))
      (node (ref "R21") (pin "2") (pinfunction "2_2") (pintype "passive"))
    )
    (net (code "63") (name "Net-(Q2-C)") (class "Default")
      (node (ref "Q2") (pin "3") (pinfunction "C_3") (pintype "passive"))
      (node (ref "SPK") (pin "1") (pinfunction "A_1") (pintype "passive"))
    )
    (net (code "64") (name "Net-(Q4-B)") (class "Default")
      (node (ref "Q4") (pin "2") (pinfunction "B_2") (pintype "passive"))
      (node (ref "R41") (pin "2") (pinfunction "2_2") (pintype "passive"))
    )
    (net (code "65") (name "Net-(Q10-B)") (class "Default")
      (node (ref "Q10") (pin "2") (pinfunction "B_2") (pintype "passive"))
      (node (ref "R10") (pin "1") (pinfunction "1_1") (pintype "passive"))
    )
    (net (code "66") (name "Net-(Q10-C)") (class "Default")
      (node (ref "Q10") (pin "3") (pinfunction "C_3") (pintype "passive"))
      (node (ref "SMG1") (pin "12") (pinfunction "C4_12") (pintype "passive"))
    )
    (net (code "67") (name "Net-(Q10-E)") (class "Default")
      (node (ref "JSM") (pin "2") (pinfunction "2_2") (pintype "passive"))
      (node (ref "Q10") (pin "1") (pinfunction "E_1") (pintype "passive"))
      (node (ref "Q11") (pin "1") (pinfunction "E_1") (pintype "passive"))
      (node (ref "Q12") (pin "1") (pinfunction "E_1") (pintype "passive"))
      (node (ref "Q13") (pin "1") (pinfunction "E_1") (pintype "passive"))
    )
    (net (code "68") (name "Net-(Q11-B)") (class "Default")
      (node (ref "Q11") (pin "2") (pinfunction "B_2") (pintype "passive"))
      (node (ref "R11") (pin "1") (pinfunction "1_1") (pintype "passive"))
    )
    (net (code "69") (name "Net-(Q11-C)") (class "Default")
      (node (ref "Q11") (pin "3") (pinfunction "C_3") (pintype "passive"))
      (node (ref "SMG1") (pin "9") (pinfunction "C3_9") (pintype "passive"))
    )
    (net (code "70") (name "Net-(Q12-B)") (class "Default")
      (node (ref "Q12") (pin "2") (pinfunction "B_2") (pintype "passive"))
      (node (ref "R12") (pin "1") (pinfunction "1_1") (pintype "passive"))
    )
    (net (code "71") (name "Net-(Q12-C)") (class "Default")
      (node (ref "Q12") (pin "3") (pinfunction "C_3") (pintype "passive"))
      (node (ref "SMG1") (pin "8") (pinfunction "C2_8") (pintype "passive"))
    )
    (net (code "72") (name "Net-(Q13-B)") (class "Default")
      (node (ref "Q13") (pin "2") (pinfunction "B_2") (pintype "passive"))
      (node (ref "R13") (pin "1") (pinfunction "1_1") (pintype "passive"))
    )
    (net (code "73") (name "Net-(Q13-C)") (class "Default")
      (node (ref "Q13") (pin "3") (pinfunction "C_3") (pintype "passive"))
      (node (ref "SMG1") (pin "6") (pinfunction "C0_6") (pintype "passive"))
    )
    (net (code "74") (name "Net-(RW1-TAP)") (class "Default")
      (node (ref "P3") (pin "3") (pinfunction "3_3") (pintype "passive"))
      (node (ref "RW1") (pin "3") (pinfunction "TAP_3") (pintype "passive"))
    )
    (net (code "75") (name "Net-(SMG1-a)") (class "Default")
      (node (ref "R31") (pin "2") (pinfunction "2_2") (pintype "passive"))
      (node (ref "SMG1") (pin "11") (pinfunction "a_11") (pintype "passive"))
    )
    (net (code "76") (name "Net-(SMG1-b)") (class "Default")
      (node (ref "R32") (pin "2") (pinfunction "2_2") (pintype "passive"))
      (node (ref "SMG1") (pin "7") (pinfunction "b_7") (pintype "passive"))
    )
    (net (code "77") (name "Net-(SMG1-c)") (class "Default")
      (node (ref "R33") (pin "2") (pinfunction "2_2") (pintype "passive"))
      (node (ref "SMG1") (pin "4") (pinfunction "c_4") (pintype "passive"))
    )
    (net (code "78") (name "Net-(SMG1-d)") (class "Default")
      (node (ref "R34") (pin "2") (pinfunction "2_2") (pintype "passive"))
      (node (ref "SMG1") (pin "2") (pinfunction "d_2") (pintype "passive"))
    )
    (net (code "79") (name "Net-(SMG1-dp)") (class "Default")
      (node (ref "R38") (pin "2") (pinfunction "2_2") (pintype "passive"))
      (node (ref "SMG1") (pin "3") (pinfunction "dp_3") (pintype "passive"))
    )
    (net (code "80") (name "Net-(SMG1-e)") (class "Default")
      (node (ref "R35") (pin "2") (pinfunction "2_2") (pintype "passive"))
      (node (ref "SMG1") (pin "1") (pinfunction "e_1") (pintype "passive"))
    )
    (net (code "81") (name "Net-(SMG1-f)") (class "Default")
      (node (ref "R36") (pin "2") (pinfunction "2_2") (pintype "passive"))
      (node (ref "SMG1") (pin "10") (pinfunction "f_10") (pintype "passive"))
    )
    (net (code "82") (name "Net-(SMG1-g)") (class "Default")
      (node (ref "R37") (pin "2") (pinfunction "2_2") (pintype "passive"))
      (node (ref "SMG1") (pin "5") (pinfunction "g_5") (pintype "passive"))
    )
    (net (code "83") (name "Net-(STC89C52-XTAL1)") (class "Default")
      (node (ref "C2") (pin "2") (pinfunction "2_2") (pintype "passive"))
      (node (ref "STC89C52") (pin "19") (pinfunction "XTAL1_19") (pintype "passive"))
      (node (ref "Y0") (pin "1") (pinfunction "1_1") (pintype "passive"))
    )
    (net (code "84") (name "Net-(STC89C52-XTAL2)") (class "Default")
      (node (ref "C3") (pin "2") (pinfunction "2_2") (pintype "passive"))
      (node (ref "STC89C52") (pin "18") (pinfunction "XTAL2_18") (pintype "passive"))
      (node (ref "Y0") (pin "2") (pinfunction "2_2") (pintype "passive"))
    )
    (net (code "85") (name "Net-(U3-UD+)") (class "Default")
      (node (ref "U3") (pin "5") (pinfunction "UD+_5") (pintype "passive"))
      (node (ref "USB") (pin "3") (pinfunction "D+_3") (pintype "passive"))
    )
    (net (code "86") (name "Net-(U3-UD-)") (class "Default")
      (node (ref "U3") (pin "6") (pinfunction "UD-_6") (pintype "passive"))
      (node (ref "USB") (pin "2") (pinfunction "D-_2") (pintype "passive"))
    )
    (net (code "87") (name "Net-(U3-X0)") (class "Default")
      (node (ref "C9") (pin "1") (pinfunction "1_1") (pintype "passive"))
      (node (ref "U3") (pin "8") (pinfunction "X0_8") (pintype "passive"))
      (node (ref "Y1") (pin "2") (pinfunction "OSC2_2") (pintype "passive"))
    )
    (net (code "88") (name "Net-(U3-X1)") (class "Default")
      (node (ref "C8") (pin "1") (pinfunction "1_1") (pintype "passive"))
      (node (ref "U3") (pin "7") (pinfunction "X1_7") (pintype "passive"))
      (node (ref "Y1") (pin "1") (pinfunction "OSC1_1") (pintype "passive"))
    )
    (net (code "89") (name "VCC") (class "Default")
      (node (ref "C1") (pin "1") (pinfunction "1_1") (pintype "passive"))
      (node (ref "C10") (pin "1") (pinfunction "1_1") (pintype "passive"))
      (node (ref "C4") (pin "1") (pinfunction "1_1") (pintype "passive"))
      (node (ref "C5") (pin "1") (pinfunction "1_1") (pintype "passive"))
      (node (ref "C6") (pin "2") (pinfunction "2_2") (pintype "passive"))
      (node (ref "D1") (pin "2") (pinfunction "K_2") (pintype "passive"))
      (node (ref "D2") (pin "1") (pinfunction "A_1") (pintype "passive"))
      (node (ref "JLED") (pin "1") (pinfunction "1_1") (pintype "passive"))
      (node (ref "JPW") (pin "4") (pinfunction "4_4") (pintype "passive"))
      (node (ref "JPW") (pin "5") (pinfunction "5_5") (pintype "passive"))
      (node (ref "JPW") (pin "6") (pinfunction "6_6") (pintype "passive"))
      (node (ref "JSM") (pin "1") (pinfunction "1_1") (pintype "passive"))
      (node (ref "P3") (pin "15") (pinfunction "15_15") (pintype "passive"))
      (node (ref "P3") (pin "2") (pinfunction "2_2") (pintype "passive"))
      (node (ref "P4") (pin "3") (pinfunction "3_3") (pintype "passive"))
      (node (ref "P5") (pin "3") (pinfunction "3_3") (pintype "passive"))
      (node (ref "Q2") (pin "1") (pinfunction "E_1") (pintype "passive"))
      (node (ref "Q4") (pin "1") (pinfunction "E_1") (pintype "passive"))
      (node (ref "R4") (pin "2") (pinfunction "2_2") (pintype "passive"))
      (node (ref "R43") (pin "2") (pinfunction "2_2") (pintype "passive"))
      (node (ref "R44") (pin "2") (pinfunction "2_2") (pintype "passive"))
      (node (ref "R45") (pin "2") (pinfunction "2_2") (pintype "passive"))
      (node (ref "RET1") (pin "2") (pinfunction "2_2") (pintype "passive"))
      (node (ref "RW1") (pin "2") (pinfunction "B_2") (pintype "passive"))
      (node (ref "STC89C52") (pin "40") (pinfunction "VCC_40") (pintype "passive"))
      (node (ref "U2") (pin "8") (pinfunction "VCC_8") (pintype "passive"))
      (node (ref "U3") (pin "16") (pinfunction "VCC_16") (pintype "passive"))
      (node (ref "USB") (pin "1") (pinfunction "+5V_1") (pintype "passive"))
    )
    (net (code "90") (name "unconnected-(U3-R232-Pad15)") (class "Default")
      (node (ref "U3") (pin "15") (pinfunction "R232_15") (pintype "passive"))
    )
    (net (code "91") (name "unconnected-(U3-~{CTS}-Pad9)") (class "Default")
      (node (ref "U3") (pin "9") (pinfunction "~{CTS}_9") (pintype "passive"))
    )
    (net (code "92") (name "unconnected-(U3-~{DCD}-Pad12)") (class "Default")
      (node (ref "U3") (pin "12") (pinfunction "~{DCD}_12") (pintype "passive"))
    )
    (net (code "93") (name "unconnected-(U3-~{DSR}-Pad10)") (class "Default")
      (node (ref "U3") (pin "10") (pinfunction "~{DSR}_10") (pintype "passive"))
    )
    (net (code "94") (name "unconnected-(U3-~{DTR}-Pad13)") (class "Default")
      (node (ref "U3") (pin "13") (pinfunction "~{DTR}_13") (pintype "passive"))
    )
    (net (code "95") (name "unconnected-(U3-~{RI}-Pad11)") (class "Default")
      (node (ref "U3") (pin "11") (pinfunction "~{RI}_11") (pintype "passive"))
    )
    (net (code "96") (name "unconnected-(U3-~{RTS}-Pad14)") (class "Default")
      (node (ref "U3") (pin "14") (pinfunction "~{RTS}_14") (pintype "passive"))
    )
  )
)
